# RC_Controller_2.net
KiCad netlist of a schematic drawn in EAGLE
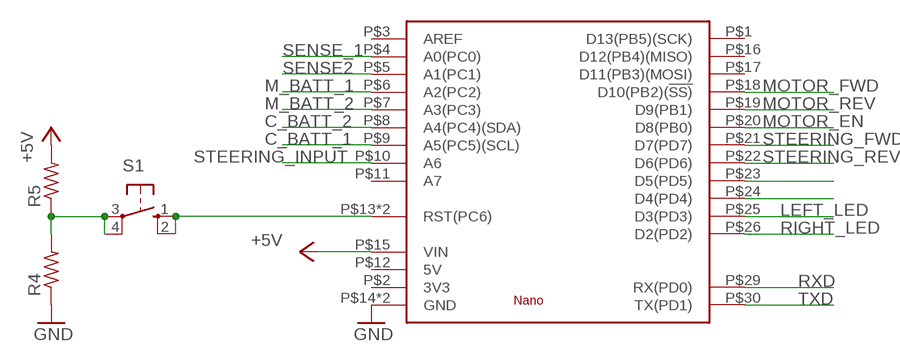
[diagram p0: schematic, sheet 1]
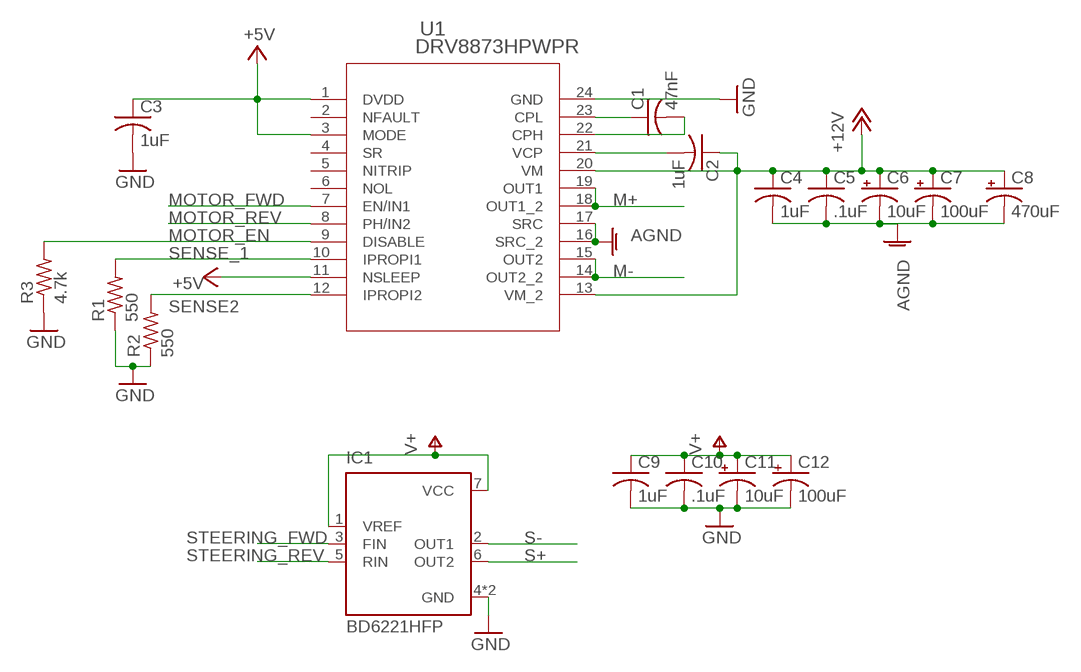
[diagram p1: schematic, sheet 2]
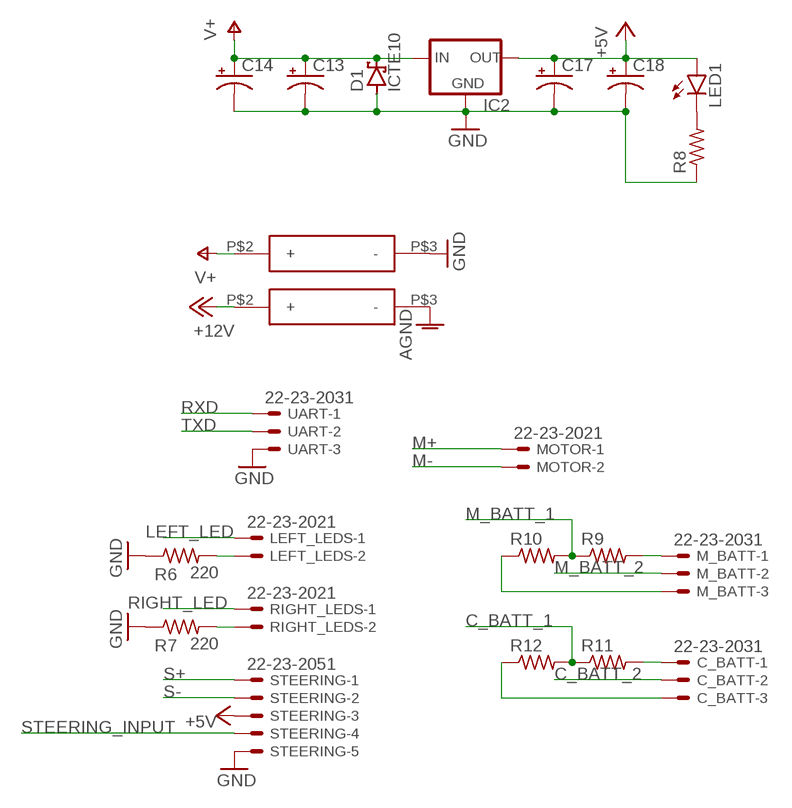
[diagram p2: schematic, sheet 3]

(export (version "E")
  (design (tool "Eeschema 10.0.6"))
  (components
    (comp (ref "C13")
      (value "CPOL-USE2.5-6")
      (footprint "eagle-import:E2,5-6")
      (libsource (lib "eagle-import") (part "CPOL-USE2.5-6"))
    )
    (comp (ref "C14")
      (value "CPOL-USE2.5-6")
      (footprint "eagle-import:E2,5-6")
      (libsource (lib "eagle-import") (part "CPOL-USE2.5-6"))
    )
    (comp (ref "C17")
      (value "CPOL-USE2.5-6")
      (footprint "eagle-import:E2,5-6")
      (libsource (lib "eagle-import") (part "CPOL-USE2.5-6"))
    )
    (comp (ref "C18")
      (value "CPOL-USE2.5-6")
      (footprint "eagle-import:E2,5-6")
      (libsource (lib "eagle-import") (part "CPOL-USE2.5-6"))
    )
    (comp (ref "C_BATT")
      (value "22-23-2031")
      (footprint "eagle-import:22-23-2031")
      (fields (field (name "MF") "MOLEX"))
      (libsource (lib "eagle-import") (part "22-23-2031"))
    )
    (comp (ref "D1")
      (value "ICTE10")
      (footprint "eagle-import:CB417-15")
      (libsource (lib "eagle-import") (part "P6KEXX"))
    )
    (comp (ref "IC2")
      (value "78XXL")
      (footprint "eagle-import:78XXL")
      (libsource (lib "eagle-import") (part "78XXL"))
    )
    (comp (ref "LED1")
      (value "LED3MM")
      (footprint "eagle-import:LED3MM")
      (libsource (lib "eagle-import") (part "LED3MM"))
    )
    (comp (ref "LEFT_LEDS")
      (value "22-23-2021")
      (footprint "eagle-import:22-23-2021")
      (fields (field (name "MF") "MOLEX"))
      (libsource (lib "eagle-import") (part "22-23-2021"))
    )
    (comp (ref "MOTOR")
      (value "22-23-2021")
      (footprint "eagle-import:22-23-2021")
      (fields (field (name "MF") "MOLEX"))
      (libsource (lib "eagle-import") (part "22-23-2021"))
    )
    (comp (ref "M_BATT")
      (value "22-23-2031")
      (footprint "eagle-import:22-23-2031")
      (fields (field (name "MF") "MOLEX"))
      (libsource (lib "eagle-import") (part "22-23-2031"))
    )
    (comp (ref "R6")
      (value "220")
      (footprint "eagle-import:0207_7")
      (libsource (lib "eagle-import") (part "R-US_0207/7"))
    )
    (comp (ref "R7")
      (value "220")
      (footprint "eagle-import:0207_7")
      (libsource (lib "eagle-import") (part "R-US_0207/7"))
    )
    (comp (ref "R8")
      (value "R-US_0207/7")
      (footprint "eagle-import:0207_7")
      (libsource (lib "eagle-import") (part "R-US_0207/7"))
    )
    (comp (ref "R9")
      (value "R-US_0207/7")
      (footprint "eagle-import:0207_7")
      (libsource (lib "eagle-import") (part "R-US_0207/7"))
    )
    (comp (ref "R10")
      (value "R-US_0207/7")
      (footprint "eagle-import:0207_7")
      (libsource (lib "eagle-import") (part "R-US_0207/7"))
    )
    (comp (ref "R11")
      (value "R-US_0207/7")
      (footprint "eagle-import:0207_7")
      (libsource (lib "eagle-import") (part "R-US_0207/7"))
    )
    (comp (ref "R12")
      (value "R-US_0207/7")
      (footprint "eagle-import:0207_7")
      (libsource (lib "eagle-import") (part "R-US_0207/7"))
    )
    (comp (ref "RIGHT_LEDS")
      (value "22-23-2021")
      (footprint "eagle-import:22-23-2021")
      (fields (field (name "MF") "MOLEX"))
      (libsource (lib "eagle-import") (part "22-23-2021"))
    )
    (comp (ref "STEERING")
      (value "22-23-2051")
      (footprint "eagle-import:22-23-2051")
      (fields (field (name "MF") "MOLEX"))
      (libsource (lib "eagle-import") (part "22-23-2051"))
    )
    (comp (ref "U$2")
      (value "BATT_TERM")
      (footprint "eagle-import:BATT_TERM")
      (libsource (lib "eagle-import") (part "BATT_TERM"))
    )
    (comp (ref "U$3")
      (value "BATT_TERM")
      (footprint "eagle-import:BATT_TERM")
      (libsource (lib "eagle-import") (part "BATT_TERM"))
    )
    (comp (ref "UART")
      (value "22-23-2031")
      (footprint "eagle-import:22-23-2031")
      (fields (field (name "MF") "MOLEX"))
      (libsource (lib "eagle-import") (part "22-23-2031"))
    )
    (comp (ref "R4")
      (value "R-US_R1206")
      (footprint "eagle-import:R1206")
      (libsource (lib "eagle-import") (part "R-US_R1206"))
    )
    (comp (ref "R5")
      (value "R-US_R1206")
      (footprint "eagle-import:R1206")
      (libsource (lib "eagle-import") (part "R-US_R1206"))
    )
    (comp (ref "S1")
      (value "10-XX")
      (footprint "eagle-import:B3F-10XX")
      (fields (field (name "MPN") "B3F-1000"))
      (libsource (lib "eagle-import") (part "10-XX"))
    )
    (comp (ref "U$1")
      (value "ARDUINO_NANO")
      (footprint "eagle-import:NANO")
      (libsource (lib "eagle-import") (part "ARDUINO_NANO"))
    )
    (comp (ref "C1")
      (value "47nF")
      (footprint "eagle-import:C1206")
      (libsource (lib "eagle-import") (part "C-USC1206"))
    )
    (comp (ref "C2")
      (value "1uF")
      (footprint "eagle-import:C1206")
      (libsource (lib "eagle-import") (part "C-USC1206"))
    )
    (comp (ref "C3")
      (value "1uF")
      (footprint "eagle-import:C1206")
      (libsource (lib "eagle-import") (part "C-USC1206"))
    )
    (comp (ref "C4")
      (value "1uF")
      (footprint "eagle-import:C1206")
      (libsource (lib "eagle-import") (part "C-USC1206"))
    )
    (comp (ref "C5")
      (value ".1uF")
      (footprint "eagle-import:C1206")
      (libsource (lib "eagle-import") (part "C-USC1206"))
    )
    (comp (ref "C6")
      (value "10uF")
      (footprint "eagle-import:E2,5-6")
      (libsource (lib "eagle-import") (part "CPOL-USE2.5-6"))
    )
    (comp (ref "C7")
      (value "100uF")
      (footprint "eagle-import:E2,5-6")
      (libsource (lib "eagle-import") (part "CPOL-USE2.5-6"))
    )
    (comp (ref "C8")
      (value "470uF")
      (footprint "eagle-import:E2,5-6")
      (libsource (lib "eagle-import") (part "CPOL-USE2.5-6"))
    )
    (comp (ref "C9")
      (value "1uF")
      (footprint "eagle-import:C1206")
      (libsource (lib "eagle-import") (part "C-USC1206"))
    )
    (comp (ref "C10")
      (value ".1uF")
      (footprint "eagle-import:C1206")
      (libsource (lib "eagle-import") (part "C-USC1206"))
    )
    (comp (ref "C11")
      (value "10uF")
      (footprint "eagle-import:E2,5-6")
      (libsource (lib "eagle-import") (part "CPOL-USE2.5-6"))
    )
    (comp (ref "C12")
      (value "100uF")
      (footprint "eagle-import:E2,5-6")
      (libsource (lib "eagle-import") (part "CPOL-USE2.5-6"))
    )
    (comp (ref "IC1")
      (value "BD6221HFP")
      (footprint "eagle-import:HRP7")
      (libsource (lib "eagle-import") (part "BD622HFP1"))
    )
    (comp (ref "R1")
      (value "550")
      (footprint "eagle-import:R1206")
      (libsource (lib "eagle-import") (part "R-US_R1206"))
    )
    (comp (ref "R2")
      (value "550")
      (footprint "eagle-import:R1206")
      (libsource (lib "eagle-import") (part "R-US_R1206"))
    )
    (comp (ref "R3")
      (value "4.7k")
      (footprint "eagle-import:R1206")
      (libsource (lib "eagle-import") (part "R-US_R1206"))
    )
    (comp (ref "U1")
      (value "DRV8873HPWPR")
      (footprint "eagle-import:PWP24_TEX")
      (fields (field (name "COPYRIGHT") "Copyright (C) 2018 Accelerated Designs. All rights reserved"))
      (libsource (lib "eagle-import") (part "DRV8873HPWPR"))
    )
  )
  (nets
    (net (code "1") (name "+5V") (class "Default")
      (node (ref "C17") (pin "+") (pinfunction "+_+") (pintype "passive"))
      (node (ref "C18") (pin "+") (pinfunction "+_+") (pintype "passive"))
      (node (ref "C3") (pin "1") (pinfunction "1_1") (pintype "passive"))
      (node (ref "IC2") (pin "OUT") (pinfunction "OUT_OUT") (pintype "passive"))
      (node (ref "LED1") (pin "A") (pinfunction "A_A") (pintype "passive"))
      (node (ref "R5") (pin "2") (pinfunction "2_2") (pintype "passive"))
      (node (ref "STEERING") (pin "3") (pinfunction "S_3") (pintype "passive"))
      (node (ref "U$1") (pin "P$15") (pinfunction "VIN_P$15") (pintype "bidirectional"))
      (node (ref "U1") (pin "1") (pinfunction "DVDD_1") (pintype "power_in"))
      (node (ref "U1") (pin "11") (pinfunction "NSLEEP_11") (pintype "input"))
      (node (ref "U1") (pin "3") (pinfunction "MODE_3") (pintype "input"))
    )
    (net (code "2") (name "+12V") (class "Default")
      (node (ref "C2") (pin "1") (pinfunction "1_1") (pintype "passive"))
      (node (ref "C4") (pin "1") (pinfunction "1_1") (pintype "passive"))
      (node (ref "C5") (pin "1") (pinfunction "1_1") (pintype "passive"))
      (node (ref "C6") (pin "+") (pinfunction "+_+") (pintype "passive"))
      (node (ref "C7") (pin "+") (pinfunction "+_+") (pintype "passive"))
      (node (ref "C8") (pin "+") (pinfunction "+_+") (pintype "passive"))
      (node (ref "U$3") (pin "P$2") (pinfunction "+_P$2") (pintype "bidirectional"))
      (node (ref "U1") (pin "13") (pinfunction "VM_2_13") (pintype "power_in"))
      (node (ref "U1") (pin "20") (pinfunction "VM_20") (pintype "power_in"))
    )
    (net (code "3") (name "AGND") (class "Default")
      (node (ref "C4") (pin "2") (pinfunction "2_2") (pintype "passive"))
      (node (ref "C5") (pin "2") (pinfunction "2_2") (pintype "passive"))
      (node (ref "C6") (pin "-") (pinfunction "-_-") (pintype "passive"))
      (node (ref "C7") (pin "-") (pinfunction "-_-") (pintype "passive"))
      (node (ref "C8") (pin "-") (pinfunction "-_-") (pintype "passive"))
      (node (ref "U$3") (pin "P$3") (pinfunction "-_P$3") (pintype "bidirectional"))
      (node (ref "U1") (pin "16") (pinfunction "SRC_2_16") (pintype "output"))
      (node (ref "U1") (pin "17") (pinfunction "SRC_17") (pintype "output"))
    )
    (net (code "4") (name "C_BATT_1") (class "Default")
      (node (ref "R11") (pin "1") (pinfunction "1_1") (pintype "passive"))
      (node (ref "R12") (pin "2") (pinfunction "2_2") (pintype "passive"))
      (node (ref "U$1") (pin "P$9") (pinfunction "A5(PC5)(SCL)_P$9") (pintype "bidirectional"))
    )
    (net (code "5") (name "C_BATT_2") (class "Default")
      (node (ref "C_BATT") (pin "2") (pinfunction "S_2") (pintype "passive"))
      (node (ref "U$1") (pin "P$8") (pinfunction "A4(PC4)(SDA)_P$8") (pintype "bidirectional"))
    )
    (net (code "6") (name "GND") (class "Default")
      (node (ref "C10") (pin "2") (pinfunction "2_2") (pintype "passive"))
      (node (ref "C11") (pin "-") (pinfunction "-_-") (pintype "passive"))
      (node (ref "C12") (pin "-") (pinfunction "-_-") (pintype "passive"))
      (node (ref "C13") (pin "-") (pinfunction "-_-") (pintype "passive"))
      (node (ref "C14") (pin "-") (pinfunction "-_-") (pintype "passive"))
      (node (ref "C17") (pin "-") (pinfunction "-_-") (pintype "passive"))
      (node (ref "C18") (pin "-") (pinfunction "-_-") (pintype "passive"))
      (node (ref "C3") (pin "2") (pinfunction "2_2") (pintype "passive"))
      (node (ref "C9") (pin "2") (pinfunction "2_2") (pintype "passive"))
      (node (ref "D1") (pin "A") (pinfunction "A_A") (pintype "passive"))
      (node (ref "IC1") (pin "4") (pinfunction "GND_4") (pintype "power_in"))
      (node (ref "IC1") (pin "P") (pinfunction "GND_P") (pintype "power_in"))
      (node (ref "IC2") (pin "GND") (pinfunction "GND_GND") (pintype "input"))
      (node (ref "R1") (pin "1") (pinfunction "1_1") (pintype "passive"))
      (node (ref "R2") (pin "1") (pinfunction "1_1") (pintype "passive"))
      (node (ref "R3") (pin "1") (pinfunction "1_1") (pintype "passive"))
      (node (ref "R4") (pin "1") (pinfunction "1_1") (pintype "passive"))
      (node (ref "R6") (pin "1") (pinfunction "1_1") (pintype "passive"))
      (node (ref "R7") (pin "1") (pinfunction "1_1") (pintype "passive"))
      (node (ref "R8") (pin "1") (pinfunction "1_1") (pintype "passive"))
      (node (ref "STEERING") (pin "5") (pinfunction "S_5") (pintype "passive"))
      (node (ref "U$1") (pin "P$14") (pinfunction "GND_P$14") (pintype "bidirectional"))
      (node (ref "U$1") (pin "P$27") (pinfunction "GND_P$27") (pintype "bidirectional"))
      (node (ref "U$2") (pin "P$3") (pinfunction "-_P$3") (pintype "bidirectional"))
      (node (ref "U1") (pin "24") (pinfunction "GND_24") (pintype "power_in"))
      (node (ref "UART") (pin "3") (pinfunction "S_3") (pintype "passive"))
    )
    (net (code "7") (name "LEFT_LED") (class "Default")
      (node (ref "LEFT_LEDS") (pin "1") (pinfunction "S_1") (pintype "passive"))
      (node (ref "U$1") (pin "P$25") (pinfunction "D3(PD3)_P$25") (pintype "bidirectional"))
    )
    (net (code "8") (name "M+") (class "Default")
      (node (ref "MOTOR") (pin "1") (pinfunction "S_1") (pintype "passive"))
      (node (ref "U1") (pin "18") (pinfunction "OUT1_2_18") (pintype "output"))
      (node (ref "U1") (pin "19") (pinfunction "OUT1_19") (pintype "output"))
    )
    (net (code "9") (name "M-") (class "Default")
      (node (ref "MOTOR") (pin "2") (pinfunction "S_2") (pintype "passive"))
      (node (ref "U1") (pin "14") (pinfunction "OUT2_2_14") (pintype "output"))
      (node (ref "U1") (pin "15") (pinfunction "OUT2_15") (pintype "output"))
    )
    (net (code "10") (name "MOTOR_EN") (class "Default")
      (node (ref "R3") (pin "2") (pinfunction "2_2") (pintype "passive"))
      (node (ref "U$1") (pin "P$20") (pinfunction "D8(PB0)_P$20") (pintype "bidirectional"))
      (node (ref "U1") (pin "9") (pinfunction "DISABLE_9") (pintype "input"))
    )
    (net (code "11") (name "MOTOR_FWD") (class "Default")
      (node (ref "U$1") (pin "P$18") (pinfunction "D10(PB2)(~{SS})_P$18") (pintype "bidirectional"))
      (node (ref "U1") (pin "7") (pinfunction "EN/IN1_7") (pintype "input"))
    )
    (net (code "12") (name "MOTOR_REV") (class "Default")
      (node (ref "U$1") (pin "P$19") (pinfunction "D9(PB1)_P$19") (pintype "bidirectional"))
      (node (ref "U1") (pin "8") (pinfunction "PH/IN2_8") (pintype "input"))
    )
    (net (code "13") (name "M_BATT_1") (class "Default")
      (node (ref "R10") (pin "2") (pinfunction "2_2") (pintype "passive"))
      (node (ref "R9") (pin "1") (pinfunction "1_1") (pintype "passive"))
      (node (ref "U$1") (pin "P$6") (pinfunction "A2(PC2)_P$6") (pintype "bidirectional"))
    )
    (net (code "14") (name "M_BATT_2") (class "Default")
      (node (ref "M_BATT") (pin "2") (pinfunction "S_2") (pintype "passive"))
      (node (ref "U$1") (pin "P$7") (pinfunction "A3(PC3)_P$7") (pintype "bidirectional"))
    )
    (net (code "15") (name "Net-(C_BATTA-S)") (class "Default")
      (node (ref "C_BATT") (pin "1") (pinfunction "S_1") (pintype "passive"))
      (node (ref "R11") (pin "2") (pinfunction "2_2") (pintype "passive"))
    )
    (net (code "16") (name "Net-(C_BATTC-S)") (class "Default")
      (node (ref "C_BATT") (pin "3") (pinfunction "S_3") (pintype "passive"))
      (node (ref "R12") (pin "1") (pinfunction "1_1") (pintype "passive"))
    )
    (net (code "17") (name "Net-(LED1-C)") (class "Default")
      (node (ref "LED1") (pin "K") (pinfunction "C_K") (pintype "passive"))
      (node (ref "R8") (pin "2") (pinfunction "2_2") (pintype "passive"))
    )
    (net (code "18") (name "Net-(LEFT_LEDSB-S)") (class "Default")
      (node (ref "LEFT_LEDS") (pin "2") (pinfunction "S_2") (pintype "passive"))
      (node (ref "R6") (pin "2") (pinfunction "2_2") (pintype "passive"))
    )
    (net (code "19") (name "Net-(M_BATTA-S)") (class "Default")
      (node (ref "M_BATT") (pin "1") (pinfunction "S_1") (pintype "passive"))
      (node (ref "R9") (pin "2") (pinfunction "2_2") (pintype "passive"))
    )
    (net (code "20") (name "Net-(M_BATTC-S)") (class "Default")
      (node (ref "M_BATT") (pin "3") (pinfunction "S_3") (pintype "passive"))
      (node (ref "R10") (pin "1") (pinfunction "1_1") (pintype "passive"))
    )
    (net (code "21") (name "Net-(RIGHT_LEDSB-S)") (class "Default")
      (node (ref "R7") (pin "2") (pinfunction "2_2") (pintype "passive"))
      (node (ref "RIGHT_LEDS") (pin "2") (pinfunction "S_2") (pintype "passive"))
    )
    (net (code "22") (name "Net-(S1-P)") (class "Default")
      (node (ref "R4") (pin "2") (pinfunction "2_2") (pintype "passive"))
      (node (ref "R5") (pin "1") (pinfunction "1_1") (pintype "passive"))
      (node (ref "S1") (pin "3") (pinfunction "P_3") (pintype "passive"))
      (node (ref "S1") (pin "4") (pinfunction "P1_4") (pintype "passive"))
    )
    (net (code "23") (name "Net-(S1-S)") (class "Default")
      (node (ref "S1") (pin "1") (pinfunction "S_1") (pintype "passive"))
      (node (ref "S1") (pin "2") (pinfunction "S1_2") (pintype "passive"))
      (node (ref "U$1") (pin "P$13") (pinfunction "RST(PC6)_P$13") (pintype "bidirectional"))
      (node (ref "U$1") (pin "P$28") (pinfunction "RST(PC6)_P$28") (pintype "bidirectional"))
    )
    (net (code "24") (name "Net-(U1-CPH)") (class "Default")
      (node (ref "C1") (pin "2") (pinfunction "2_2") (pintype "passive"))
      (node (ref "U1") (pin "22") (pinfunction "CPH_22") (pintype "passive"))
    )
    (net (code "25") (name "Net-(U1-CPL)") (class "Default")
      (node (ref "C1") (pin "1") (pinfunction "1_1") (pintype "passive"))
      (node (ref "U1") (pin "23") (pinfunction "CPL_23") (pintype "passive"))
    )
    (net (code "26") (name "Net-(U1-VCP)") (class "Default")
      (node (ref "C2") (pin "2") (pinfunction "2_2") (pintype "passive"))
      (node (ref "U1") (pin "21") (pinfunction "VCP_21") (pintype "power_in"))
    )
    (net (code "27") (name "RIGHT_LED") (class "Default")
      (node (ref "RIGHT_LEDS") (pin "1") (pinfunction "S_1") (pintype "passive"))
      (node (ref "U$1") (pin "P$26") (pinfunction "D2(PD2)_P$26") (pintype "bidirectional"))
    )
    (net (code "28") (name "RXD") (class "Default")
      (node (ref "U$1") (pin "P$29") (pinfunction "RX(PD0)_P$29") (pintype "bidirectional"))
      (node (ref "UART") (pin "1") (pinfunction "S_1") (pintype "passive"))
    )
    (net (code "29") (name "S+") (class "Default")
      (node (ref "IC1") (pin "6") (pinfunction "OUT2_6") (pintype "output"))
      (node (ref "STEERING") (pin "1") (pinfunction "S_1") (pintype "passive"))
    )
    (net (code "30") (name "S-") (class "Default")
      (node (ref "IC1") (pin "2") (pinfunction "OUT1_2") (pintype "output"))
      (node (ref "STEERING") (pin "2") (pinfunction "S_2") (pintype "passive"))
    )
    (net (code "31") (name "SENSE2") (class "Default")
      (node (ref "R2") (pin "2") (pinfunction "2_2") (pintype "passive"))
      (node (ref "U$1") (pin "P$5") (pinfunction "A1(PC1)_P$5") (pintype "bidirectional"))
      (node (ref "U1") (pin "12") (pinfunction "IPROPI2_12") (pintype "output"))
    )
    (net (code "32") (name "SENSE_1") (class "Default")
      (node (ref "R1") (pin "2") (pinfunction "2_2") (pintype "passive"))
      (node (ref "U$1") (pin "P$4") (pinfunction "A0(PC0)_P$4") (pintype "bidirectional"))
      (node (ref "U1") (pin "10") (pinfunction "IPROPI1_10") (pintype "output"))
    )
    (net (code "33") (name "STEERING_FWD") (class "Default")
      (node (ref "IC1") (pin "3") (pinfunction "FIN_3") (pintype "input"))
      (node (ref "U$1") (pin "P$21") (pinfunction "D7(PD7)_P$21") (pintype "bidirectional"))
    )
    (net (code "34") (name "STEERING_INPUT") (class "Default")
      (node (ref "STEERING") (pin "4") (pinfunction "S_4") (pintype "passive"))
      (node (ref "U$1") (pin "P$10") (pinfunction "A6_P$10") (pintype "bidirectional"))
    )
    (net (code "35") (name "STEERING_REV") (class "Default")
      (node (ref "IC1") (pin "5") (pinfunction "RIN_5") (pintype "input"))
      (node (ref "U$1") (pin "P$22") (pinfunction "D6(PD6)_P$22") (pintype "bidirectional"))
    )
    (net (code "36") (name "TXD") (class "Default")
      (node (ref "U$1") (pin "P$30") (pinfunction "TX(PD1)_P$30") (pintype "bidirectional"))
      (node (ref "UART") (pin "2") (pinfunction "S_2") (pintype "passive"))
    )
    (net (code "37") (name "V+") (class "Default")
      (node (ref "C10") (pin "1") (pinfunction "1_1") (pintype "passive"))
      (node (ref "C11") (pin "+") (pinfunction "+_+") (pintype "passive"))
      (node (ref "C12") (pin "+") (pinfunction "+_+") (pintype "passive"))
      (node (ref "C13") (pin "+") (pinfunction "+_+") (pintype "passive"))
      (node (ref "C14") (pin "+") (pinfunction "+_+") (pintype "passive"))
      (node (ref "C9") (pin "1") (pinfunction "1_1") (pintype "passive"))
      (node (ref "D1") (pin "C") (pinfunction "C_C") (pintype "passive"))
      (node (ref "IC1") (pin "1") (pinfunction "VREF_1") (pintype "passive"))
      (node (ref "IC1") (pin "7") (pinfunction "VCC_7") (pintype "power_in"))
      (node (ref "IC2") (pin "IN") (pinfunction "IN_IN") (pintype "input"))
      (node (ref "U$2") (pin "P$2") (pinfunction "+_P$2") (pintype "bidirectional"))
    )
    (net (code "38") (name "unconnected-(U$1-3V3-PadP$2)") (class "Default")
      (node (ref "U$1") (pin "P$2") (pinfunction "3V3_P$2") (pintype "bidirectional"))
    )
    (net (code "39") (name "unconnected-(U$1-5V-PadP$12)") (class "Default")
      (node (ref "U$1") (pin "P$12") (pinfunction "5V_P$12") (pintype "bidirectional"))
    )
    (net (code "40") (name "unconnected-(U$1-A7-PadP$11)") (class "Default")
      (node (ref "U$1") (pin "P$11") (pinfunction "A7_P$11") (pintype "bidirectional"))
    )
    (net (code "41") (name "unconnected-(U$1-AREF-PadP$3)") (class "Default")
      (node (ref "U$1") (pin "P$3") (pinfunction "AREF_P$3") (pintype "bidirectional"))
    )
    (net (code "42") (name "unconnected-(U$1-D4(PD4)-PadP$24)") (class "Default")
      (node (ref "U$1") (pin "P$24") (pinfunction "D4(PD4)_P$24") (pintype "bidirectional"))
    )
    (net (code "43") (name "unconnected-(U$1-D5(PD5)-PadP$23)") (class "Default")
      (node (ref "U$1") (pin "P$23") (pinfunction "D5(PD5)_P$23") (pintype "bidirectional"))
    )
    (net (code "44") (name "unconnected-(U$1-D11(PB3)(MOSI)-PadP$17)") (class "Default")
      (node (ref "U$1") (pin "P$17") (pinfunction "D11(PB3)(MOSI)_P$17") (pintype "bidirectional"))
    )
    (net (code "45") (name "unconnected-(U$1-D12(PB4)(MISO)-PadP$16)") (class "Default")
      (node (ref "U$1") (pin "P$16") (pinfunction "D12(PB4)(MISO)_P$16") (pintype "bidirectional"))
    )
    (net (code "46") (name "unconnected-(U$1-D13(PB5)(SCK)-PadP$1)") (class "Default")
      (node (ref "U$1") (pin "P$1") (pinfunction "D13(PB5)(SCK)_P$1") (pintype "bidirectional"))
    )
    (net (code "47") (name "unconnected-(U1-NFAULT-Pad2)") (class "Default")
      (node (ref "U1") (pin "2") (pinfunction "NFAULT_2") (pintype "output"))
    )
    (net (code "48") (name "unconnected-(U1-NITRIP-Pad5)") (class "Default")
      (node (ref "U1") (pin "5") (pinfunction "NITRIP_5") (pintype "input"))
    )
    (net (code "49") (name "unconnected-(U1-NOL-Pad6)") (class "Default")
      (node (ref "U1") (pin "6") (pinfunction "NOL_6") (pintype "input"))
    )
    (net (code "50") (name "unconnected-(U1-SR-Pad4)") (class "Default")
      (node (ref "U1") (pin "4") (pinfunction "SR_4") (pintype "input"))
    )
  )
)
